# 5V_Power_Stage.net
KiCad netlist of a schematic drawn in Altium Designer
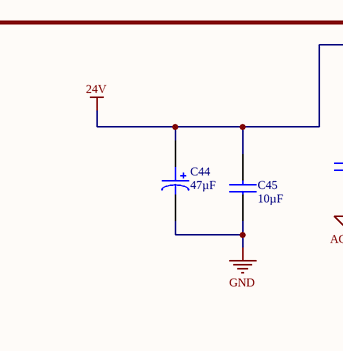
[diagram p0: 5V_Power_Stage.SchDoc, left]
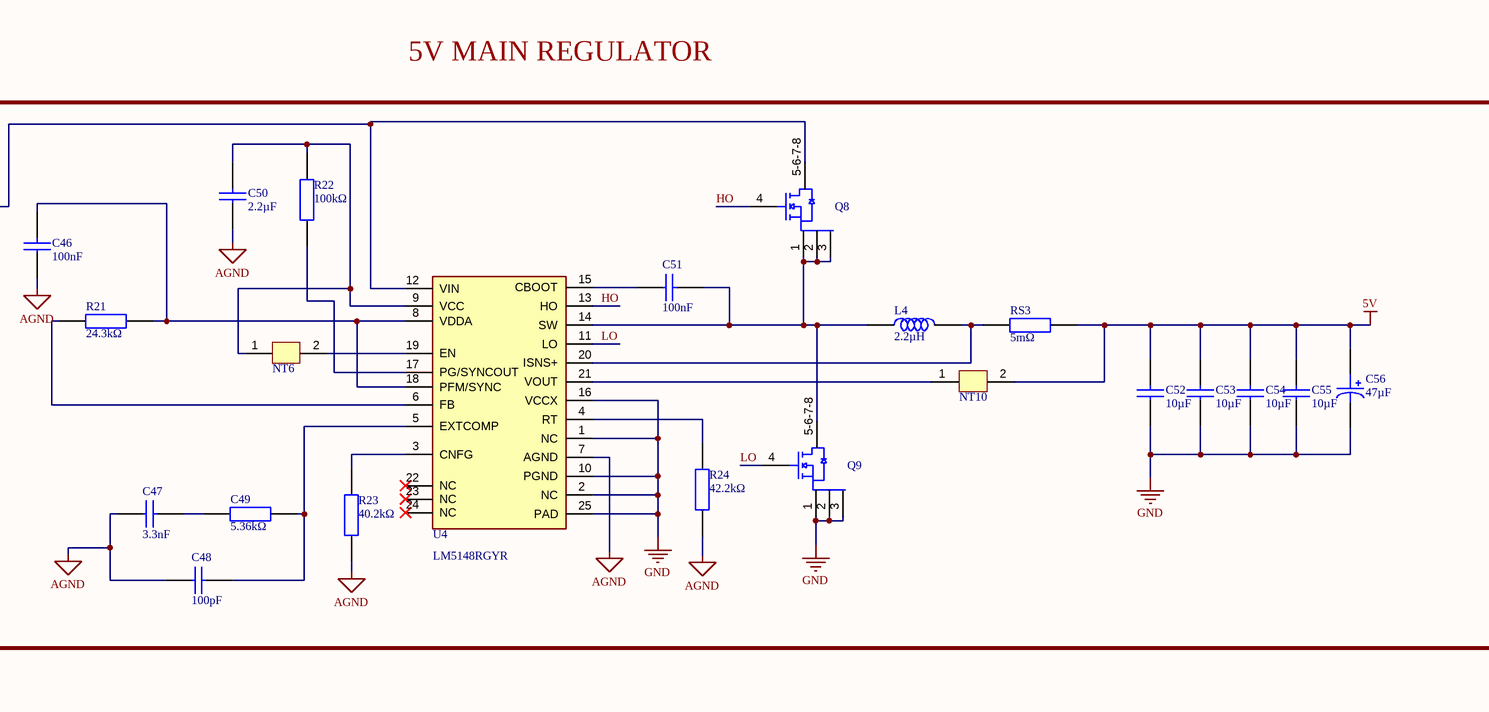
[diagram p1: 5V_Power_Stage.SchDoc, right]

(export (version "E")
  (design (tool "Eeschema 10.0.6"))
  (components
    (comp (ref "C44")
      (value "47µF")
      (footprint "CAP ALUM SMD")
      (description "Conductive Polymer Hybrid Aluminum Electrolytic Capacitors, 47µF, 50V, -55 to 105¡C")
      (fields
        (field (name "MANUFACTURER") "Panasonic")
        (field (name "MANUFACTURER PART NUMBER") "EEH-ZA1H470P")
      )
      (libsource (lib "PDU_BOM") (part "EEHZA1H470P"))
    )
    (comp (ref "C45")
      (value "10µF")
      (footprint "CAP_1206")
      (description "50V 10uF X7R 卤10% 1206 Multilayer Ceramic Capacitors MLCC - SMD/SMT ROHS")
      (fields
        (field (name "MANUFACTURER") "TDK")
        (field (name "MANUFACTURER PART NUMBER") "C3216X7R1H106K160AC")
      )
      (libsource (lib "PDU_BOM") (part "C3216X7R1H106K160AC"))
    )
    (comp (ref "C46")
      (value "100nF")
      (footprint "CAP_0402")
      (description "10V 100nF X7R ±10% 0402 Multilayer Ceramic Capacitors MLCC - SMD/SMT ROHS")
      (fields
        (field (name "MANUFACTURER") "Murata")
        (field (name "MANUFACTURER PART NUMBER") "GRM155R71A104KA01D")
      )
      (libsource (lib "PDU_BOM") (part "GRM155R71A104KA01D"))
    )
    (comp (ref "C47")
      (value "3.3nF")
      (footprint "CAP_0805")
      (description "50V 3.3nF C0G 卤5% 0805 Multilayer Ceramic Capacitors MLCC - SMD/SMT ROHS")
      (fields
        (field (name "MANUFACTURER") "TDK")
        (field (name "MANUFACTURER PART NUMBER") "CGA4C2C0G1H332J060AA")
      )
      (libsource (lib "PDU_BOM") (part "CGA4C2C0G1H332J060AA"))
    )
    (comp (ref "C48")
      (value "100pF")
      (footprint "CAP_0805")
      (description "50V 100pF C0G 卤5% 0805 Multilayer Ceramic Capacitors MLCC - SMD/SMT ROHS")
      (fields
        (field (name "MANUFACTURER") "Samsung Electro-Mechanics")
        (field (name "MANUFACTURER PART NUMBER") "CL21C101JBANNNC")
      )
      (libsource (lib "PDU_BOM") (part "CL21C101JBANNNC"))
    )
    (comp (ref "C49")
      (value "5.36kΩ")
      (footprint "RES_0402")
      (description "Res Thick Film 0402 5.36K Ohm 1% 0.063W(1/16W) ±100ppm/C Pad SMD T/R Automotive AEC-Q200")
      (fields
        (field (name "MANUFACTURER") "Vishay")
        (field (name "MANUFACTURER PART NUMBER") "CRCW04025K36FKED")
      )
      (libsource (lib "PDU_BOM") (part "CRCW04025K36FKED"))
    )
    (comp (ref "C50")
      (value "2.2µF")
      (footprint "CAP_0603")
      (description "10V 2.2uF X7R ±10% 0603 Multilayer Ceramic Capacitors MLCC - SMD/SMT ROHS")
      (fields
        (field (name "MANUFACTURER") "Murata")
        (field (name "MANUFACTURER PART NUMBER") "GRM188R71A225KE15D")
      )
      (libsource (lib "PDU_BOM") (part "GRM188R71A225KE15D"))
    )
    (comp (ref "C51")
      (value "100nF")
      (footprint "CAP_0402")
      (description "10V 100nF X7R ±10% 0402 Multilayer Ceramic Capacitors MLCC - SMD/SMT ROHS")
      (fields
        (field (name "MANUFACTURER") "Murata")
        (field (name "MANUFACTURER PART NUMBER") "GRM155R71A104KA01D")
      )
      (libsource (lib "PDU_BOM") (part "GRM155R71A104KA01D"))
    )
    (comp (ref "C52")
      (value "10µF")
      (footprint "CAP_1206")
      (description "25V 10uF X7R ±10% 1206 Multilayer Ceramic Capacitors MLCC - SMD/SMT ROHS")
      (fields
        (field (name "MANUFACTURER") "Murata")
        (field (name "MANUFACTURER PART NUMBER") "GRM31CR71E106KA12L")
      )
      (libsource (lib "PDU_BOM") (part "GRM31CR71E106KA12L"))
    )
    (comp (ref "C53")
      (value "10µF")
      (footprint "CAP_1206")
      (description "25V 10uF X7R ±10% 1206 Multilayer Ceramic Capacitors MLCC - SMD/SMT ROHS")
      (fields
        (field (name "MANUFACTURER") "Murata")
        (field (name "MANUFACTURER PART NUMBER") "GRM31CR71E106KA12L")
      )
      (libsource (lib "PDU_BOM") (part "GRM31CR71E106KA12L"))
    )
    (comp (ref "C54")
      (value "10µF")
      (footprint "CAP_1206")
      (description "25V 10uF X7R ±10% 1206 Multilayer Ceramic Capacitors MLCC - SMD/SMT ROHS")
      (fields
        (field (name "MANUFACTURER") "Murata")
        (field (name "MANUFACTURER PART NUMBER") "GRM31CR71E106KA12L")
      )
      (libsource (lib "PDU_BOM") (part "GRM31CR71E106KA12L"))
    )
    (comp (ref "C55")
      (value "10µF")
      (footprint "CAP_1206")
      (description "25V 10uF X7R ±10% 1206 Multilayer Ceramic Capacitors MLCC - SMD/SMT ROHS")
      (fields
        (field (name "MANUFACTURER") "Murata")
        (field (name "MANUFACTURER PART NUMBER") "GRM31CR71E106KA12L")
      )
      (libsource (lib "PDU_BOM") (part "GRM31CR71E106KA12L"))
    )
    (comp (ref "C56")
      (value "47µF")
      (footprint "CAP ALUM SMD")
      (description "Conductive Polymer Hybrid Aluminum Electrolytic Capacitors, 47µF, 50V, -55 to 105¡C")
      (fields
        (field (name "MANUFACTURER") "Panasonic")
        (field (name "MANUFACTURER PART NUMBER") "EEH-ZA1H470P")
      )
      (libsource (lib "PDU_BOM") (part "EEHZA1H470P"))
    )
    (comp (ref "L4")
      (value "2.2µH")
      (footprint "XAL7070")
      (description "General Purpose Inductor, 2.2uH, 20%, 1 Element, Composite-Core, SMD, 3028")
      (fields
        (field (name "MANUFACTURER") "Coilcraft")
        (field (name "MANUFACTURER PART NUMBER") "XAL7070-222MEB")
      )
      (libsource (lib "PDU_BOM") (part "XAL7070-222MEC"))
    )
    (comp (ref "NT6") (value "Net-Tie") (footprint "Net-Tie") (libsource (lib "PDU_BOM") (part "Net-Tie")))
    (comp (ref "NT10") (value "Net-Tie") (footprint "Net-Tie") (libsource (lib "PDU_BOM") (part "Net-Tie")))
    (comp (ref "Q8")
      (value "CSD18540Q5B")
      (footprint "SON 5X6")
      (description "60-V, N channel NexFET™ power MOSFET, single SON 5 mm x 6 mm, 2.2 mOhm 8-VSON-CLIP -55 to 175")
      (fields (field (name "MANUFACTURER") "Texas Instruments"))
      (libsource (lib "PDU_BOM") (part "CSD18540Q5B"))
    )
    (comp (ref "Q9")
      (value "CSD18563Q5A")
      (footprint "SON 5X6")
      (description "60-V, N channel NexFET™ power MOSFET, single SON 5 mm x 6 mm, 6.8 mOhm 8-VSONP -55 to 150")
      (fields (field (name "MANUFACTURER") "Texas Instruments"))
      (libsource (lib "PDU_BOM") (part "CSD18563Q5A"))
    )
    (comp (ref "R21")
      (value "24.3kΩ")
      (footprint "RES_0402")
      (description "Fixed Resistor, Metal Glaze/Thick Film, 0.063W, 24300ohm, 50V, 1% +/-Tol, Surface Mount, 0402")
      (fields
        (field (name "MANUFACTURER") "Vishay")
        (field (name "MANUFACTURER PART NUMBER") "CRCW040224K3FKED")
      )
      (libsource (lib "PDU_BOM") (part "CRCW040224K3FKED"))
    )
    (comp (ref "R22")
      (value "100kΩ")
      (footprint "RES_0603")
      (description "Res Thick Film 0603 100K Ohm 1% 1/3W ±100ppm/°C Molded SMD SMD Paper T/R")
      (fields
        (field (name "MANUFACTURER") "Vishay")
        (field (name "MANUFACTURER PART NUMBER") "CRCW0603100KFKEAHP")
      )
      (libsource (lib "PDU_BOM") (part "CRCW0603100KFKEA"))
    )
    (comp (ref "R23")
      (value "40.2kΩ")
      (footprint "RES_0603")
      (description "Res Thick Film 0603 40.2K Ohm 1% 0.1W(1/10W) ±100ppm/C Pad SMD T/R")
      (fields
        (field (name "MANUFACTURER") "Yageo Group")
        (field (name "MANUFACTURER PART NUMBER") "RC0603FR-0740K2L")
      )
      (libsource (lib "PDU_BOM") (part "RC0603FR-0740K2L"))
    )
    (comp (ref "R24")
      (value "42.2kΩ")
      (footprint "RES_0603")
      (description "Res Thick Film 0603 42.2K Ohm 1% 1/10W ±100ppm/°C Molded SMD Paper T/R")
      (fields
        (field (name "MANUFACTURER") "Vishay")
        (field (name "MANUFACTURER PART NUMBER") "CRCW060342K2FKEA")
      )
      (libsource (lib "PDU_BOM") (part "CRCW060342K2FKEA"))
    )
    (comp (ref "RS3")
      (value "5mΩ")
      (footprint "RES_2010")
      (description "Res Metal Foil 2010 0.005 Ohm 1% 1.5W ±50ppm/°C Molded SMD SMD Plastic T/R")
      (fields
        (field (name "MANUFACTURER") "Stackpole Electronics")
        (field (name "MANUFACTURER PART NUMBER") "CSNL2010FT5L00")
      )
      (libsource (lib "PDU_BOM") (part "CSNL2010FT5L00"))
    )
    (comp (ref "U4")
      (value "LM5148RGYR")
      (footprint "VQFN-24")
      (description "3.5-V to 80-V, current mode synchronous buck controller 24-VQFN -40 to 125")
      (fields (field (name "MANUFACTURER") "Texas Instruments"))
      (libsource (lib "PDU_BOM") (part "LM5148RGYR"))
    )
  )
  (nets
    (net (code "1") (name "/HO") (class "Default")
      (node (ref "Q8") (pin "4") (pinfunction "G_4") (pintype "passive"))
      (node (ref "U4") (pin "13") (pinfunction "HO_13") (pintype "passive"))
    )
    (net (code "2") (name "/LO") (class "Default")
      (node (ref "Q9") (pin "4") (pinfunction "G_4") (pintype "passive"))
      (node (ref "U4") (pin "11") (pinfunction "LO_11") (pintype "passive"))
    )
    (net (code "3") (name "5V") (class "Default")
      (node (ref "C52") (pin "2") (pinfunction "2_2") (pintype "passive"))
      (node (ref "C53") (pin "2") (pinfunction "2_2") (pintype "passive"))
      (node (ref "C54") (pin "2") (pinfunction "2_2") (pintype "passive"))
      (node (ref "C55") (pin "2") (pinfunction "2_2") (pintype "passive"))
      (node (ref "C56") (pin "1") (pinfunction "C_1") (pintype "passive"))
      (node (ref "NT10") (pin "2") (pinfunction "2_2") (pintype "passive"))
      (node (ref "RS3") (pin "2") (pinfunction "2_2") (pintype "passive"))
    )
    (net (code "4") (name "24V") (class "Default")
      (node (ref "C44") (pin "1") (pinfunction "C_1") (pintype "passive"))
      (node (ref "C45") (pin "2") (pinfunction "2_2") (pintype "passive"))
      (node (ref "Q8") (pin "5-6-7-8") (pinfunction "D_5-6-7-8") (pintype "passive"))
      (node (ref "U4") (pin "12") (pinfunction "VIN_12") (pintype "passive"))
    )
    (net (code "5") (name "AGND") (class "Default")
      (node (ref "C46") (pin "1") (pinfunction "1_1") (pintype "passive"))
      (node (ref "C47") (pin "1") (pinfunction "1_1") (pintype "passive"))
      (node (ref "C48") (pin "1") (pinfunction "1_1") (pintype "passive"))
      (node (ref "C50") (pin "1") (pinfunction "1_1") (pintype "passive"))
      (node (ref "R23") (pin "1") (pinfunction "1_1") (pintype "passive"))
      (node (ref "R24") (pin "1") (pinfunction "1_1") (pintype "passive"))
      (node (ref "U4") (pin "7") (pinfunction "AGND_7") (pintype "passive"))
    )
    (net (code "6") (name "GND") (class "Default")
      (node (ref "C44") (pin "2") (pinfunction "A_2") (pintype "passive"))
      (node (ref "C45") (pin "1") (pinfunction "1_1") (pintype "passive"))
      (node (ref "C52") (pin "1") (pinfunction "1_1") (pintype "passive"))
      (node (ref "C53") (pin "1") (pinfunction "1_1") (pintype "passive"))
      (node (ref "C54") (pin "1") (pinfunction "1_1") (pintype "passive"))
      (node (ref "C55") (pin "1") (pinfunction "1_1") (pintype "passive"))
      (node (ref "C56") (pin "2") (pinfunction "A_2") (pintype "passive"))
      (node (ref "Q9") (pin "1") (pinfunction "S_1") (pintype "passive"))
      (node (ref "Q9") (pin "2") (pinfunction "S_2") (pintype "passive"))
      (node (ref "Q9") (pin "3") (pinfunction "S_3") (pintype "passive"))
      (node (ref "U4") (pin "1") (pinfunction "NC_1") (pintype "passive"))
      (node (ref "U4") (pin "10") (pinfunction "PGND_10") (pintype "passive"))
      (node (ref "U4") (pin "16") (pinfunction "VCCX_16") (pintype "passive"))
      (node (ref "U4") (pin "2") (pinfunction "NC_2") (pintype "passive"))
      (node (ref "U4") (pin "25") (pinfunction "PAD_25") (pintype "passive"))
    )
    (net (code "7") (name "Net-(C47-Pad2)") (class "Default")
      (node (ref "C47") (pin "2") (pinfunction "2_2") (pintype "passive"))
      (node (ref "C49") (pin "1") (pinfunction "1_1") (pintype "passive"))
    )
    (net (code "8") (name "Net-(Q9-D)") (class "Default")
      (node (ref "C51") (pin "2") (pinfunction "2_2") (pintype "passive"))
      (node (ref "L4") (pin "1") (pinfunction "1_1") (pintype "passive"))
      (node (ref "Q8") (pin "1") (pinfunction "S_1") (pintype "passive"))
      (node (ref "Q8") (pin "2") (pinfunction "S_2") (pintype "passive"))
      (node (ref "Q8") (pin "3") (pinfunction "S_3") (pintype "passive"))
      (node (ref "Q9") (pin "5-6-7-8") (pinfunction "D_5-6-7-8") (pintype "passive"))
      (node (ref "U4") (pin "14") (pinfunction "SW_14") (pintype "passive"))
    )
    (net (code "9") (name "Net-(U4-CBOOT)") (class "Default")
      (node (ref "C51") (pin "1") (pinfunction "1_1") (pintype "passive"))
      (node (ref "U4") (pin "15") (pinfunction "CBOOT_15") (pintype "passive"))
    )
    (net (code "10") (name "Net-(U4-CNFG)") (class "Default")
      (node (ref "R23") (pin "2") (pinfunction "2_2") (pintype "passive"))
      (node (ref "U4") (pin "3") (pinfunction "CNFG_3") (pintype "passive"))
    )
    (net (code "11") (name "Net-(U4-EN)") (class "Default")
      (node (ref "NT6") (pin "2") (pinfunction "2_2") (pintype "passive"))
      (node (ref "U4") (pin "19") (pinfunction "EN_19") (pintype "passive"))
    )
    (net (code "12") (name "Net-(U4-EXTCOMP)") (class "Default")
      (node (ref "C48") (pin "2") (pinfunction "2_2") (pintype "passive"))
      (node (ref "C49") (pin "2") (pinfunction "2_2") (pintype "passive"))
      (node (ref "U4") (pin "5") (pinfunction "EXTCOMP_5") (pintype "passive"))
    )
    (net (code "13") (name "Net-(U4-FB)") (class "Default")
      (node (ref "R21") (pin "1") (pinfunction "1_1") (pintype "passive"))
      (node (ref "U4") (pin "6") (pinfunction "FB_6") (pintype "passive"))
    )
    (net (code "14") (name "Net-(U4-ISNS+)") (class "Default")
      (node (ref "L4") (pin "2") (pinfunction "2_2") (pintype "passive"))
      (node (ref "RS3") (pin "1") (pinfunction "1_1") (pintype "passive"))
      (node (ref "U4") (pin "20") (pinfunction "ISNS+_20") (pintype "passive"))
    )
    (net (code "15") (name "Net-(U4-PFM{slash}SYNC)") (class "Default")
      (node (ref "C46") (pin "2") (pinfunction "2_2") (pintype "passive"))
      (node (ref "R21") (pin "2") (pinfunction "2_2") (pintype "passive"))
      (node (ref "U4") (pin "18") (pinfunction "PFM/SYNC_18") (pintype "passive"))
      (node (ref "U4") (pin "8") (pinfunction "VDDA_8") (pintype "passive"))
    )
    (net (code "16") (name "Net-(U4-PG{slash}SYNCOUT)") (class "Default")
      (node (ref "R22") (pin "1") (pinfunction "1_1") (pintype "passive"))
      (node (ref "U4") (pin "17") (pinfunction "PG/SYNCOUT_17") (pintype "passive"))
    )
    (net (code "17") (name "Net-(U4-RT)") (class "Default")
      (node (ref "R24") (pin "2") (pinfunction "2_2") (pintype "passive"))
      (node (ref "U4") (pin "4") (pinfunction "RT_4") (pintype "passive"))
    )
    (net (code "18") (name "Net-(U4-VCC)") (class "Default")
      (node (ref "C50") (pin "2") (pinfunction "2_2") (pintype "passive"))
      (node (ref "NT6") (pin "1") (pinfunction "1_1") (pintype "passive"))
      (node (ref "R22") (pin "2") (pinfunction "2_2") (pintype "passive"))
      (node (ref "U4") (pin "9") (pinfunction "VCC_9") (pintype "passive"))
    )
    (net (code "19") (name "Net-(U4-VOUT)") (class "Default")
      (node (ref "NT10") (pin "1") (pinfunction "1_1") (pintype "passive"))
      (node (ref "U4") (pin "21") (pinfunction "VOUT_21") (pintype "passive"))
    )
    (net (code "20") (name "unconnected-(U4-NC-Pad22)") (class "Default")
      (node (ref "U4") (pin "22") (pinfunction "NC_22") (pintype "passive+no_connect"))
    )
    (net (code "21") (name "unconnected-(U4-NC-Pad23)") (class "Default")
      (node (ref "U4") (pin "23") (pinfunction "NC_23") (pintype "passive+no_connect"))
    )
    (net (code "22") (name "unconnected-(U4-NC-Pad24)") (class "Default")
      (node (ref "U4") (pin "24") (pinfunction "NC_24") (pintype "passive+no_connect"))
    )
  )
)
